# Zigbee_broad.net
KiCad netlist of a schematic drawn in Altium Designer
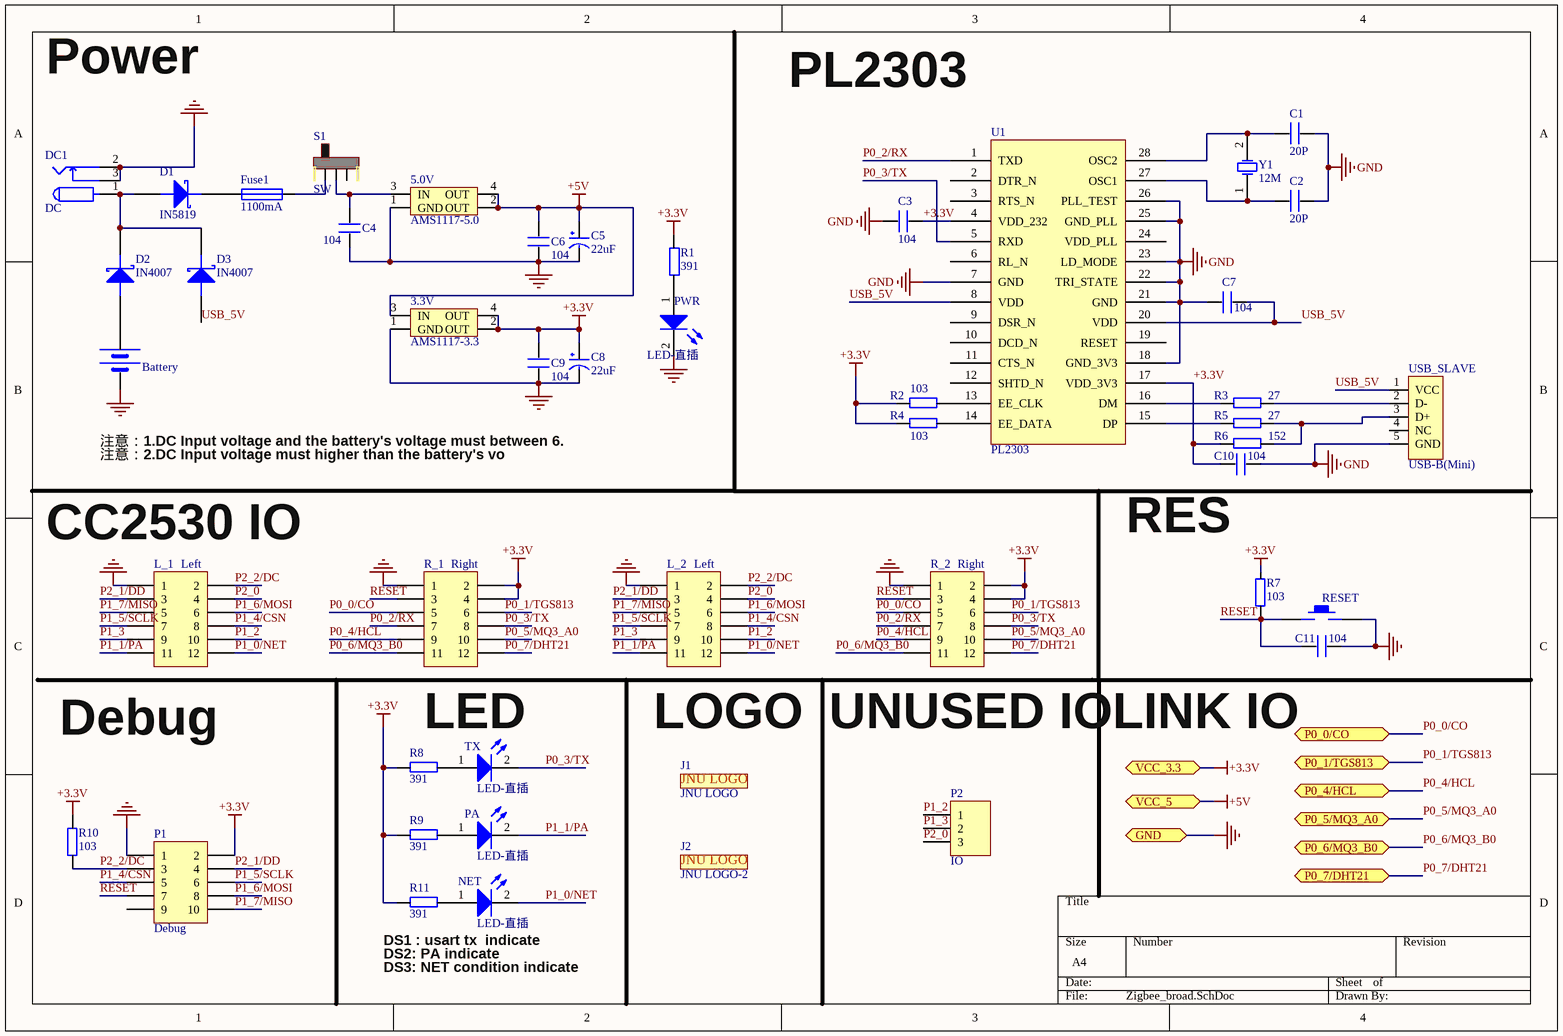
[diagram p0: Zigbee_broad.SchDoc]

(export (version "E")
  (design (tool "Eeschema 10.0.6"))
  (components
    (comp (ref "3.3V")
      (value "AMS1117-3.3")
      (footprint "AMS1117")
      (description "3.3V 5V:输入6.5V-12V")
      (libsource (lib "SEA_SCH_LIB") (part "AMS1117"))
    )
    (comp (ref "5.0V")
      (value "AMS1117-5.0")
      (footprint "AMS1117")
      (description "3.3V 5V:输入6.5V-12V")
      (libsource (lib "SEA_SCH_LIB") (part "AMS1117"))
    )
    (comp (ref "Battery") (value "BATT") (footprint "DC") (libsource (lib "SEA_SCH_LIB") (part "BAT")))
    (comp (ref "C1")
      (value "20P")
      (footprint "0603")
      (description "CAP")
      (libsource (lib "SEA_SCH_LIB") (part "CAP"))
    )
    (comp (ref "C2")
      (value "20P")
      (footprint "0603")
      (description "CAP")
      (libsource (lib "SEA_SCH_LIB") (part "CAP"))
    )
    (comp (ref "C3")
      (value "104")
      (footprint "0603")
      (description "CAP")
      (libsource (lib "SEA_SCH_LIB") (part "CAP"))
    )
    (comp (ref "C4")
      (value "104")
      (footprint "0603")
      (description "CAP")
      (libsource (lib "SEA_SCH_LIB") (part "CAP"))
    )
    (comp (ref "C5") (value "22uF") (footprint "Cap2") (libsource (lib "SEA_SCH_LIB") (part "CAP-2")))
    (comp (ref "C6")
      (value "104")
      (footprint "0603")
      (description "CAP")
      (libsource (lib "SEA_SCH_LIB") (part "CAP"))
    )
    (comp (ref "C7")
      (value "104")
      (footprint "0603")
      (description "CAP")
      (libsource (lib "SEA_SCH_LIB") (part "CAP"))
    )
    (comp (ref "C8") (value "22uF") (footprint "Cap2") (libsource (lib "SEA_SCH_LIB") (part "CAP-2")))
    (comp (ref "C9")
      (value "104")
      (footprint "0603")
      (description "CAP")
      (libsource (lib "SEA_SCH_LIB") (part "CAP"))
    )
    (comp (ref "C10")
      (value "104")
      (footprint "0603")
      (description "CAP")
      (libsource (lib "SEA_SCH_LIB") (part "CAP"))
    )
    (comp (ref "C11")
      (value "104")
      (footprint "0603")
      (description "CAP")
      (libsource (lib "SEA_SCH_LIB") (part "CAP"))
    )
    (comp (ref "D1")
      (value "IN5819")
      (footprint "IN4007 M7")
      (description "Schottky Diode")
      (libsource (lib "SEA_SCH_LIB") (part "DIODE SCHOTTKY"))
    )
    (comp (ref "D2")
      (value "IN4007")
      (footprint "IN4007 M7")
      (description "Schottky Diode")
      (libsource (lib "SEA_SCH_LIB") (part "DIODE SCHOTTKY"))
    )
    (comp (ref "D3")
      (value "IN4007")
      (footprint "IN4007 M7")
      (description "Schottky Diode")
      (libsource (lib "SEA_SCH_LIB") (part "DIODE SCHOTTKY"))
    )
    (comp (ref "DC1") (value "DC") (footprint "DC") (libsource (lib "SEA_SCH_LIB") (part "DC")))
    (comp (ref "Fuse1")
      (value "1100mA")
      (footprint "1812")
      (description "保险丝，保险丝的封装有很多，注意")
      (libsource (lib "SEA_SCH_LIB") (part "FUSH"))
    )
    (comp (ref "J1")
      (value "JNU LOGO")
      (footprint "JNU LOGO - 1")
      (description "JNU logo")
      (libsource (lib "SEA_SCH_LIB") (part "JNU LOGO"))
    )
    (comp (ref "J2")
      (value "JNU LOGO-2")
      (footprint "JNU LOGO - 1")
      (description "JNU logo")
      (libsource (lib "SEA_SCH_LIB") (part "JNU LOGO"))
    )
    (comp (ref "L_1")
      (value "Left")
      (footprint "HDR2X6")
      (description "Header, 6-Pin, Dual row")
      (fields (field (name "PUBLISHER") "Altium Limited"))
      (libsource (lib "Miscellaneous Connectors") (part "Header 6X2"))
    )
    (comp (ref "L_2")
      (value "Left")
      (footprint "HDR2X6")
      (description "Header, 6-Pin, Dual row")
      (fields (field (name "PUBLISHER") "Altium Limited"))
      (libsource (lib "Miscellaneous Connectors") (part "Header 6X2"))
    )
    (comp (ref "NET") (value "LED-直插") (footprint "LED") (libsource (lib "SEA_SCH_LIB") (part "LED-直插")))
    (comp (ref "P1")
      (value "Debug")
      (footprint "Header 2*5")
      (description "Header, 5-Pin, Dual row")
      (fields (field (name "PUBLISHER") "Altium Limited"))
      (libsource (lib "SEA_SCH_LIB") (part "Header 5X2"))
    )
    (comp (ref "P2")
      (value "IO")
      (footprint "HDR1X3")
      (description "Header, 3-Pin")
      (fields (field (name "PUBLISHER") "Altium Limited"))
      (libsource (lib "Miscellaneous Connectors") (part "Header 3"))
    )
    (comp (ref "PA") (value "LED-直插") (footprint "LED") (libsource (lib "SEA_SCH_LIB") (part "LED-直插")))
    (comp (ref "PWR") (value "LED-直插") (footprint "LED") (libsource (lib "SEA_SCH_LIB") (part "LED-直插")))
    (comp (ref "R1") (value "391") (footprint "0603") (libsource (lib "SEA_SCH_LIB") (part "Resistor")))
    (comp (ref "R2") (value "103") (footprint "0603") (libsource (lib "SEA_SCH_LIB") (part "Resistor")))
    (comp (ref "R3") (value "27") (footprint "0603") (libsource (lib "SEA_SCH_LIB") (part "Resistor")))
    (comp (ref "R4") (value "103") (footprint "0603") (libsource (lib "SEA_SCH_LIB") (part "Resistor")))
    (comp (ref "R5") (value "27") (footprint "0603") (libsource (lib "SEA_SCH_LIB") (part "Resistor")))
    (comp (ref "R6") (value "152") (footprint "0603") (libsource (lib "SEA_SCH_LIB") (part "Resistor")))
    (comp (ref "R7") (value "103") (footprint "0603") (libsource (lib "SEA_SCH_LIB") (part "Resistor")))
    (comp (ref "R8") (value "391") (footprint "0603") (libsource (lib "SEA_SCH_LIB") (part "Resistor")))
    (comp (ref "R9") (value "391") (footprint "0603") (libsource (lib "SEA_SCH_LIB") (part "Resistor")))
    (comp (ref "R10") (value "103") (footprint "0603") (libsource (lib "SEA_SCH_LIB") (part "Resistor")))
    (comp (ref "R11") (value "391") (footprint "0603") (libsource (lib "SEA_SCH_LIB") (part "Resistor")))
    (comp (ref "RESET")
      (value "KEY_M")
      (footprint "KEY_M")
      (libsource (lib "ALIENTEK_COMPONENT") (part "KEY_M"))
    )
    (comp (ref "R_1")
      (value "Right")
      (footprint "HDR2X6")
      (description "Header, 6-Pin, Dual row")
      (fields (field (name "PUBLISHER") "Altium Limited"))
      (libsource (lib "Miscellaneous Connectors") (part "Header 6X2"))
    )
    (comp (ref "R_2")
      (value "Right")
      (footprint "HDR2X6")
      (description "Header, 6-Pin, Dual row")
      (fields (field (name "PUBLISHER") "Altium Limited"))
      (libsource (lib "Miscellaneous Connectors") (part "Header 6X2"))
    )
    (comp (ref "S1")
      (value "SW")
      (footprint "switch")
      (description "微拨开关")
      (libsource (lib "SEA_SCH_LIB") (part "SWITCH-2"))
    )
    (comp (ref "TX") (value "LED-直插") (footprint "LED") (libsource (lib "SEA_SCH_LIB") (part "LED-直插")))
    (comp (ref "U1")
      (value "PL2303")
      (footprint "PL2303 -SOP28N")
      (libsource (lib "SEA_SCH_LIB") (part "PL2303"))
    )
    (comp (ref "USB_SLAVE")
      (value "USB-B(Mini)")
      (footprint "MINI_USB - 1")
      (libsource (lib "SEA_SCH_LIB") (part "USB_MINI"))
    )
    (comp (ref "Y1")
      (value "12M")
      (footprint "XTAL")
      (description "Crystal Oscillator")
      (fields (field (name "PUBLISHER") "Altium Limited"))
      (libsource (lib "SEA_SCH_LIB") (part "XTAL"))
    )
  )
  (nets
    (net (code "1") (name "+3.3V") (class "Default")
      (node (ref "3.3V") (pin "2") (pinfunction "OUT_2") (pintype "passive"))
      (node (ref "3.3V") (pin "4") (pinfunction "OUT_4") (pintype "passive"))
      (node (ref "C10") (pin "2") (pintype "passive"))
      (node (ref "C3") (pin "1") (pintype "passive"))
      (node (ref "C8") (pin "1") (pinfunction "VCC_1") (pintype "passive"))
      (node (ref "C9") (pin "2") (pintype "passive"))
      (node (ref "P1") (pin "2") (pinfunction "2_2") (pintype "passive"))
      (node (ref "R1") (pin "2") (pintype "passive"))
      (node (ref "R10") (pin "1") (pintype "passive"))
      (node (ref "R11") (pin "2") (pintype "passive"))
      (node (ref "R2") (pin "2") (pintype "passive"))
      (node (ref "R4") (pin "2") (pintype "passive"))
      (node (ref "R6") (pin "2") (pintype "passive"))
      (node (ref "R7") (pin "1") (pintype "passive"))
      (node (ref "R8") (pin "2") (pintype "passive"))
      (node (ref "R9") (pin "2") (pintype "passive"))
      (node (ref "R_1") (pin "2") (pinfunction "2_2") (pintype "passive"))
      (node (ref "R_1") (pin "4") (pinfunction "4_4") (pintype "passive"))
      (node (ref "R_2") (pin "2") (pinfunction "2_2") (pintype "passive"))
      (node (ref "R_2") (pin "4") (pinfunction "4_4") (pintype "passive"))
      (node (ref "U1") (pin "17") (pinfunction "VDD_3V3_17") (pintype "passive"))
      (node (ref "U1") (pin "4") (pinfunction "VDD_232_4") (pintype "passive"))
    )
    (net (code "2") (name "+5V") (class "Default")
      (node (ref "3.3V") (pin "3") (pinfunction "IN_3") (pintype "passive"))
      (node (ref "5.0V") (pin "2") (pinfunction "OUT_2") (pintype "passive"))
      (node (ref "5.0V") (pin "4") (pinfunction "OUT_4") (pintype "passive"))
      (node (ref "C5") (pin "1") (pinfunction "VCC_1") (pintype "passive"))
      (node (ref "C6") (pin "2") (pintype "passive"))
    )
    (net (code "3") (name "/P0_0{slash}CO") (class "Default")
      (node (ref "R_1") (pin "5") (pinfunction "5_5") (pintype "passive"))
      (node (ref "R_2") (pin "5") (pinfunction "5_5") (pintype "passive"))
    )
    (net (code "4") (name "/P0_1{slash}TGS813") (class "Default")
      (node (ref "R_1") (pin "6") (pinfunction "6_6") (pintype "passive"))
      (node (ref "R_2") (pin "6") (pinfunction "6_6") (pintype "passive"))
    )
    (net (code "5") (name "/P0_2{slash}RX") (class "Default")
      (node (ref "R_1") (pin "7") (pinfunction "7_7") (pintype "passive"))
      (node (ref "R_2") (pin "7") (pinfunction "7_7") (pintype "passive"))
      (node (ref "U1") (pin "1") (pinfunction "TXD_1") (pintype "passive"))
    )
    (net (code "6") (name "/P0_3{slash}TX") (class "Default")
      (node (ref "R_1") (pin "8") (pinfunction "8_8") (pintype "passive"))
      (node (ref "R_2") (pin "8") (pinfunction "8_8") (pintype "passive"))
      (node (ref "TX") (pin "2") (pinfunction "2_2") (pintype "passive"))
      (node (ref "U1") (pin "5") (pinfunction "RXD_5") (pintype "passive"))
    )
    (net (code "7") (name "/P0_4{slash}HCL") (class "Default")
      (node (ref "R_1") (pin "9") (pinfunction "9_9") (pintype "passive"))
      (node (ref "R_2") (pin "9") (pinfunction "9_9") (pintype "passive"))
    )
    (net (code "8") (name "/P0_5{slash}MQ3_A0") (class "Default")
      (node (ref "R_1") (pin "10") (pinfunction "10_10") (pintype "passive"))
      (node (ref "R_2") (pin "10") (pinfunction "10_10") (pintype "passive"))
    )
    (net (code "9") (name "/P0_6{slash}MQ3_B0") (class "Default")
      (node (ref "R_1") (pin "11") (pinfunction "11_11") (pintype "passive"))
      (node (ref "R_2") (pin "11") (pinfunction "11_11") (pintype "passive"))
    )
    (net (code "10") (name "/P0_7{slash}DHT21") (class "Default")
      (node (ref "R_1") (pin "12") (pinfunction "12_12") (pintype "passive"))
      (node (ref "R_2") (pin "12") (pinfunction "12_12") (pintype "passive"))
    )
    (net (code "11") (name "/P1_0{slash}NET") (class "Default")
      (node (ref "L_1") (pin "12") (pinfunction "12_12") (pintype "passive"))
      (node (ref "L_2") (pin "12") (pinfunction "12_12") (pintype "passive"))
      (node (ref "NET") (pin "2") (pinfunction "2_2") (pintype "passive"))
    )
    (net (code "12") (name "/P1_1{slash}PA") (class "Default")
      (node (ref "L_1") (pin "11") (pinfunction "11_11") (pintype "passive"))
      (node (ref "L_2") (pin "11") (pinfunction "11_11") (pintype "passive"))
      (node (ref "PA") (pin "2") (pinfunction "2_2") (pintype "passive"))
    )
    (net (code "13") (name "/P1_2") (class "Default")
      (node (ref "L_1") (pin "10") (pinfunction "10_10") (pintype "passive"))
      (node (ref "L_2") (pin "10") (pinfunction "10_10") (pintype "passive"))
      (node (ref "P2") (pin "1") (pinfunction "1_1") (pintype "passive"))
    )
    (net (code "14") (name "/P1_3") (class "Default")
      (node (ref "L_1") (pin "9") (pinfunction "9_9") (pintype "passive"))
      (node (ref "L_2") (pin "9") (pinfunction "9_9") (pintype "passive"))
      (node (ref "P2") (pin "2") (pinfunction "2_2") (pintype "passive"))
    )
    (net (code "15") (name "/P1_4{slash}CSN") (class "Default")
      (node (ref "L_1") (pin "8") (pinfunction "8_8") (pintype "passive"))
      (node (ref "L_2") (pin "8") (pinfunction "8_8") (pintype "passive"))
      (node (ref "P1") (pin "5") (pinfunction "5_5") (pintype "passive"))
    )
    (net (code "16") (name "/P1_5{slash}SCLK") (class "Default")
      (node (ref "L_1") (pin "7") (pinfunction "7_7") (pintype "passive"))
      (node (ref "L_2") (pin "7") (pinfunction "7_7") (pintype "passive"))
      (node (ref "P1") (pin "6") (pinfunction "6_6") (pintype "passive"))
    )
    (net (code "17") (name "/P1_6{slash}MOSI") (class "Default")
      (node (ref "L_1") (pin "6") (pinfunction "6_6") (pintype "passive"))
      (node (ref "L_2") (pin "6") (pinfunction "6_6") (pintype "passive"))
      (node (ref "P1") (pin "8") (pinfunction "8_8") (pintype "passive"))
    )
    (net (code "18") (name "/P1_7{slash}MISO") (class "Default")
      (node (ref "L_1") (pin "5") (pinfunction "5_5") (pintype "passive"))
      (node (ref "L_2") (pin "5") (pinfunction "5_5") (pintype "passive"))
      (node (ref "P1") (pin "10") (pinfunction "10_10") (pintype "passive"))
    )
    (net (code "19") (name "/P2_0") (class "Default")
      (node (ref "L_1") (pin "4") (pinfunction "4_4") (pintype "passive"))
      (node (ref "L_2") (pin "4") (pinfunction "4_4") (pintype "passive"))
      (node (ref "P2") (pin "3") (pinfunction "3_3") (pintype "passive"))
    )
    (net (code "20") (name "/P2_1{slash}DD") (class "Default")
      (node (ref "L_1") (pin "3") (pinfunction "3_3") (pintype "passive"))
      (node (ref "L_2") (pin "3") (pinfunction "3_3") (pintype "passive"))
      (node (ref "P1") (pin "4") (pinfunction "4_4") (pintype "passive"))
    )
    (net (code "21") (name "/P2_2{slash}DC") (class "Default")
      (node (ref "L_1") (pin "2") (pinfunction "2_2") (pintype "passive"))
      (node (ref "L_2") (pin "2") (pinfunction "2_2") (pintype "passive"))
      (node (ref "P1") (pin "3") (pinfunction "3_3") (pintype "passive"))
      (node (ref "R10") (pin "2") (pintype "passive"))
    )
    (net (code "22") (name "/RESET") (class "Default")
      (node (ref "C11") (pin "2") (pintype "passive"))
      (node (ref "P1") (pin "7") (pinfunction "7_7") (pintype "passive"))
      (node (ref "R7") (pin "2") (pintype "passive"))
      (node (ref "RESET") (pin "1") (pinfunction "1_1") (pintype "passive"))
      (node (ref "R_1") (pin "3") (pinfunction "3_3") (pintype "passive"))
      (node (ref "R_2") (pin "3") (pinfunction "3_3") (pintype "passive"))
    )
    (net (code "23") (name "/USB_5V") (class "Default")
      (node (ref "C7") (pin "1") (pintype "passive"))
      (node (ref "D3") (pin "1") (pinfunction "1_1") (pintype "passive"))
      (node (ref "U1") (pin "20") (pinfunction "VDD_20") (pintype "passive"))
      (node (ref "U1") (pin "8") (pinfunction "VDD_8") (pintype "passive"))
      (node (ref "USB_SLAVE") (pin "1") (pinfunction "VCC_1") (pintype "passive"))
    )
    (net (code "24") (name "GND") (class "Default")
      (node (ref "3.3V") (pin "1") (pinfunction "GND_1") (pintype "passive"))
      (node (ref "5.0V") (pin "1") (pinfunction "GND_1") (pintype "passive"))
      (node (ref "Battery") (pin "2") (pinfunction "GND_2") (pintype "passive"))
      (node (ref "C1") (pin "1") (pintype "passive"))
      (node (ref "C10") (pin "1") (pintype "passive"))
      (node (ref "C11") (pin "1") (pintype "passive"))
      (node (ref "C2") (pin "1") (pintype "passive"))
      (node (ref "C3") (pin "2") (pintype "passive"))
      (node (ref "C4") (pin "1") (pintype "passive"))
      (node (ref "C5") (pin "2") (pinfunction "GND_2") (pintype "passive"))
      (node (ref "C6") (pin "1") (pintype "passive"))
      (node (ref "C7") (pin "2") (pintype "passive"))
      (node (ref "C8") (pin "2") (pinfunction "GND_2") (pintype "passive"))
      (node (ref "C9") (pin "1") (pintype "passive"))
      (node (ref "DC1") (pin "2") (pintype "passive"))
      (node (ref "DC1") (pin "3") (pintype "passive"))
      (node (ref "L_1") (pin "1") (pinfunction "1_1") (pintype "passive"))
      (node (ref "L_2") (pin "1") (pinfunction "1_1") (pintype "passive"))
      (node (ref "P1") (pin "1") (pinfunction "1_1") (pintype "passive"))
      (node (ref "PWR") (pin "2") (pinfunction "2_2") (pintype "passive"))
      (node (ref "RESET") (pin "2") (pinfunction "2_2") (pintype "passive"))
      (node (ref "R_1") (pin "1") (pinfunction "1_1") (pintype "passive"))
      (node (ref "R_2") (pin "1") (pinfunction "1_1") (pintype "passive"))
      (node (ref "U1") (pin "18") (pinfunction "GND_3V3_18") (pintype "passive"))
      (node (ref "U1") (pin "21") (pinfunction "GND_21") (pintype "passive"))
      (node (ref "U1") (pin "22") (pinfunction "TRI_STATE_22") (pintype "passive"))
      (node (ref "U1") (pin "23") (pinfunction "LD_MODE_23") (pintype "passive"))
      (node (ref "U1") (pin "25") (pinfunction "GND_PLL_25") (pintype "passive"))
      (node (ref "U1") (pin "26") (pinfunction "PLL_TEST_26") (pintype "passive"))
      (node (ref "U1") (pin "7") (pinfunction "GND_7") (pintype "passive"))
      (node (ref "USB_SLAVE") (pin "5") (pinfunction "GND_5") (pintype "passive"))
    )
    (net (code "25") (name "Net-(5.0V-IN)") (class "Default")
      (node (ref "5.0V") (pin "3") (pinfunction "IN_3") (pintype "passive"))
      (node (ref "C4") (pin "2") (pintype "passive"))
      (node (ref "S1") (pin "2") (pinfunction "2_2") (pintype "passive"))
    )
    (net (code "26") (name "Net-(Battery-VCC)") (class "Default")
      (node (ref "Battery") (pin "1") (pinfunction "VCC_1") (pintype "passive"))
      (node (ref "D2") (pin "1") (pinfunction "1_1") (pintype "passive"))
    )
    (net (code "27") (name "Net-(D1-Pad1)") (class "Default")
      (node (ref "D1") (pin "1") (pinfunction "1_1") (pintype "passive"))
      (node (ref "D2") (pin "2") (pinfunction "2_2") (pintype "passive"))
      (node (ref "D3") (pin "2") (pinfunction "2_2") (pintype "passive"))
      (node (ref "DC1") (pin "1") (pintype "passive"))
    )
    (net (code "28") (name "Net-(D1-Pad2)") (class "Default")
      (node (ref "D1") (pin "2") (pinfunction "2_2") (pintype "passive"))
      (node (ref "Fuse1") (pin "1") (pinfunction "1_1") (pintype "passive"))
    )
    (net (code "29") (name "Net-(Fuse1-Pad2)") (class "Default")
      (node (ref "Fuse1") (pin "2") (pinfunction "2_2") (pintype "passive"))
      (node (ref "S1") (pin "1") (pinfunction "1_1") (pintype "passive"))
    )
    (net (code "30") (name "Net-(NET-Pad1)") (class "Default")
      (node (ref "NET") (pin "1") (pinfunction "1_1") (pintype "passive"))
      (node (ref "R11") (pin "1") (pintype "passive"))
    )
    (net (code "31") (name "Net-(PA-Pad1)") (class "Default")
      (node (ref "PA") (pin "1") (pinfunction "1_1") (pintype "passive"))
      (node (ref "R9") (pin "1") (pintype "passive"))
    )
    (net (code "32") (name "Net-(PWR-Pad1)") (class "Default")
      (node (ref "PWR") (pin "1") (pinfunction "1_1") (pintype "passive"))
      (node (ref "R1") (pin "1") (pintype "passive"))
    )
    (net (code "33") (name "Net-(R8-Pad1)") (class "Default")
      (node (ref "R8") (pin "1") (pintype "passive"))
      (node (ref "TX") (pin "1") (pinfunction "1_1") (pintype "passive"))
    )
    (net (code "34") (name "Net-(U1-DM)") (class "Default")
      (node (ref "R3") (pin "2") (pintype "passive"))
      (node (ref "U1") (pin "16") (pinfunction "DM_16") (pintype "passive"))
    )
    (net (code "35") (name "Net-(U1-DP)") (class "Default")
      (node (ref "R5") (pin "2") (pintype "passive"))
      (node (ref "U1") (pin "15") (pinfunction "DP_15") (pintype "passive"))
    )
    (net (code "36") (name "Net-(U1-EE_CLK)") (class "Default")
      (node (ref "R2") (pin "1") (pintype "passive"))
      (node (ref "U1") (pin "13") (pinfunction "EE_CLK_13") (pintype "passive"))
    )
    (net (code "37") (name "Net-(U1-EE_DATA)") (class "Default")
      (node (ref "R4") (pin "1") (pintype "passive"))
      (node (ref "U1") (pin "14") (pinfunction "EE_DATA_14") (pintype "passive"))
    )
    (net (code "38") (name "Net-(U1-OSC1)") (class "Default")
      (node (ref "C2") (pin "2") (pintype "passive"))
      (node (ref "U1") (pin "27") (pinfunction "OSC1_27") (pintype "passive"))
      (node (ref "Y1") (pin "1") (pinfunction "OSC1_1") (pintype "passive"))
    )
    (net (code "39") (name "Net-(U1-OSC2)") (class "Default")
      (node (ref "C1") (pin "2") (pintype "passive"))
      (node (ref "U1") (pin "28") (pinfunction "OSC2_28") (pintype "passive"))
      (node (ref "Y1") (pin "2") (pinfunction "OSC2_2") (pintype "passive"))
    )
    (net (code "40") (name "Net-(USB_SLAVE-D+)") (class "Default")
      (node (ref "R5") (pin "1") (pintype "passive"))
      (node (ref "R6") (pin "1") (pintype "passive"))
      (node (ref "USB_SLAVE") (pin "3") (pinfunction "D+_3") (pintype "passive"))
    )
    (net (code "41") (name "Net-(USB_SLAVE-D-)") (class "Default")
      (node (ref "R3") (pin "1") (pintype "passive"))
      (node (ref "USB_SLAVE") (pin "2") (pinfunction "D-_2") (pintype "passive"))
    )
    (net (code "42") (name "unconnected-(P1-Pad9)") (class "Default")
      (node (ref "P1") (pin "9") (pinfunction "9_9") (pintype "passive"))
    )
    (net (code "43") (name "unconnected-(S1-Pad3)") (class "Default")
      (node (ref "S1") (pin "3") (pinfunction "3_3") (pintype "passive"))
    )
    (net (code "44") (name "unconnected-(U1-CTS_N-Pad11)") (class "Default")
      (node (ref "U1") (pin "11") (pinfunction "CTS_N_11") (pintype "passive"))
    )
    (net (code "45") (name "unconnected-(U1-DCD_N-Pad10)") (class "Default")
      (node (ref "U1") (pin "10") (pinfunction "DCD_N_10") (pintype "passive"))
    )
    (net (code "46") (name "unconnected-(U1-DSR_N-Pad9)") (class "Default")
      (node (ref "U1") (pin "9") (pinfunction "DSR_N_9") (pintype "passive"))
    )
    (net (code "47") (name "unconnected-(U1-DTR_N-Pad2)") (class "Default")
      (node (ref "U1") (pin "2") (pinfunction "DTR_N_2") (pintype "passive"))
    )
    (net (code "48") (name "unconnected-(U1-RESET-Pad19)") (class "Default")
      (node (ref "U1") (pin "19") (pinfunction "RESET_19") (pintype "passive"))
    )
    (net (code "49") (name "unconnected-(U1-RL_N-Pad6)") (class "Default")
      (node (ref "U1") (pin "6") (pinfunction "RL_N_6") (pintype "passive"))
    )
    (net (code "50") (name "unconnected-(U1-RTS_N-Pad3)") (class "Default")
      (node (ref "U1") (pin "3") (pinfunction "RTS_N_3") (pintype "passive"))
    )
    (net (code "51") (name "unconnected-(U1-SHTD_N-Pad12)") (class "Default")
      (node (ref "U1") (pin "12") (pinfunction "SHTD_N_12") (pintype "passive"))
    )
    (net (code "52") (name "unconnected-(U1-VDD_PLL-Pad24)") (class "Default")
      (node (ref "U1") (pin "24") (pinfunction "VDD_PLL_24") (pintype "passive"))
    )
    (net (code "53") (name "unconnected-(USB_SLAVE-NC-Pad4)") (class "Default")
      (node (ref "USB_SLAVE") (pin "4") (pinfunction "NC_4") (pintype "passive"))
    )
  )
)
